# Camera_IR.net
KiCad netlist of a schematic drawn in EasyEDA
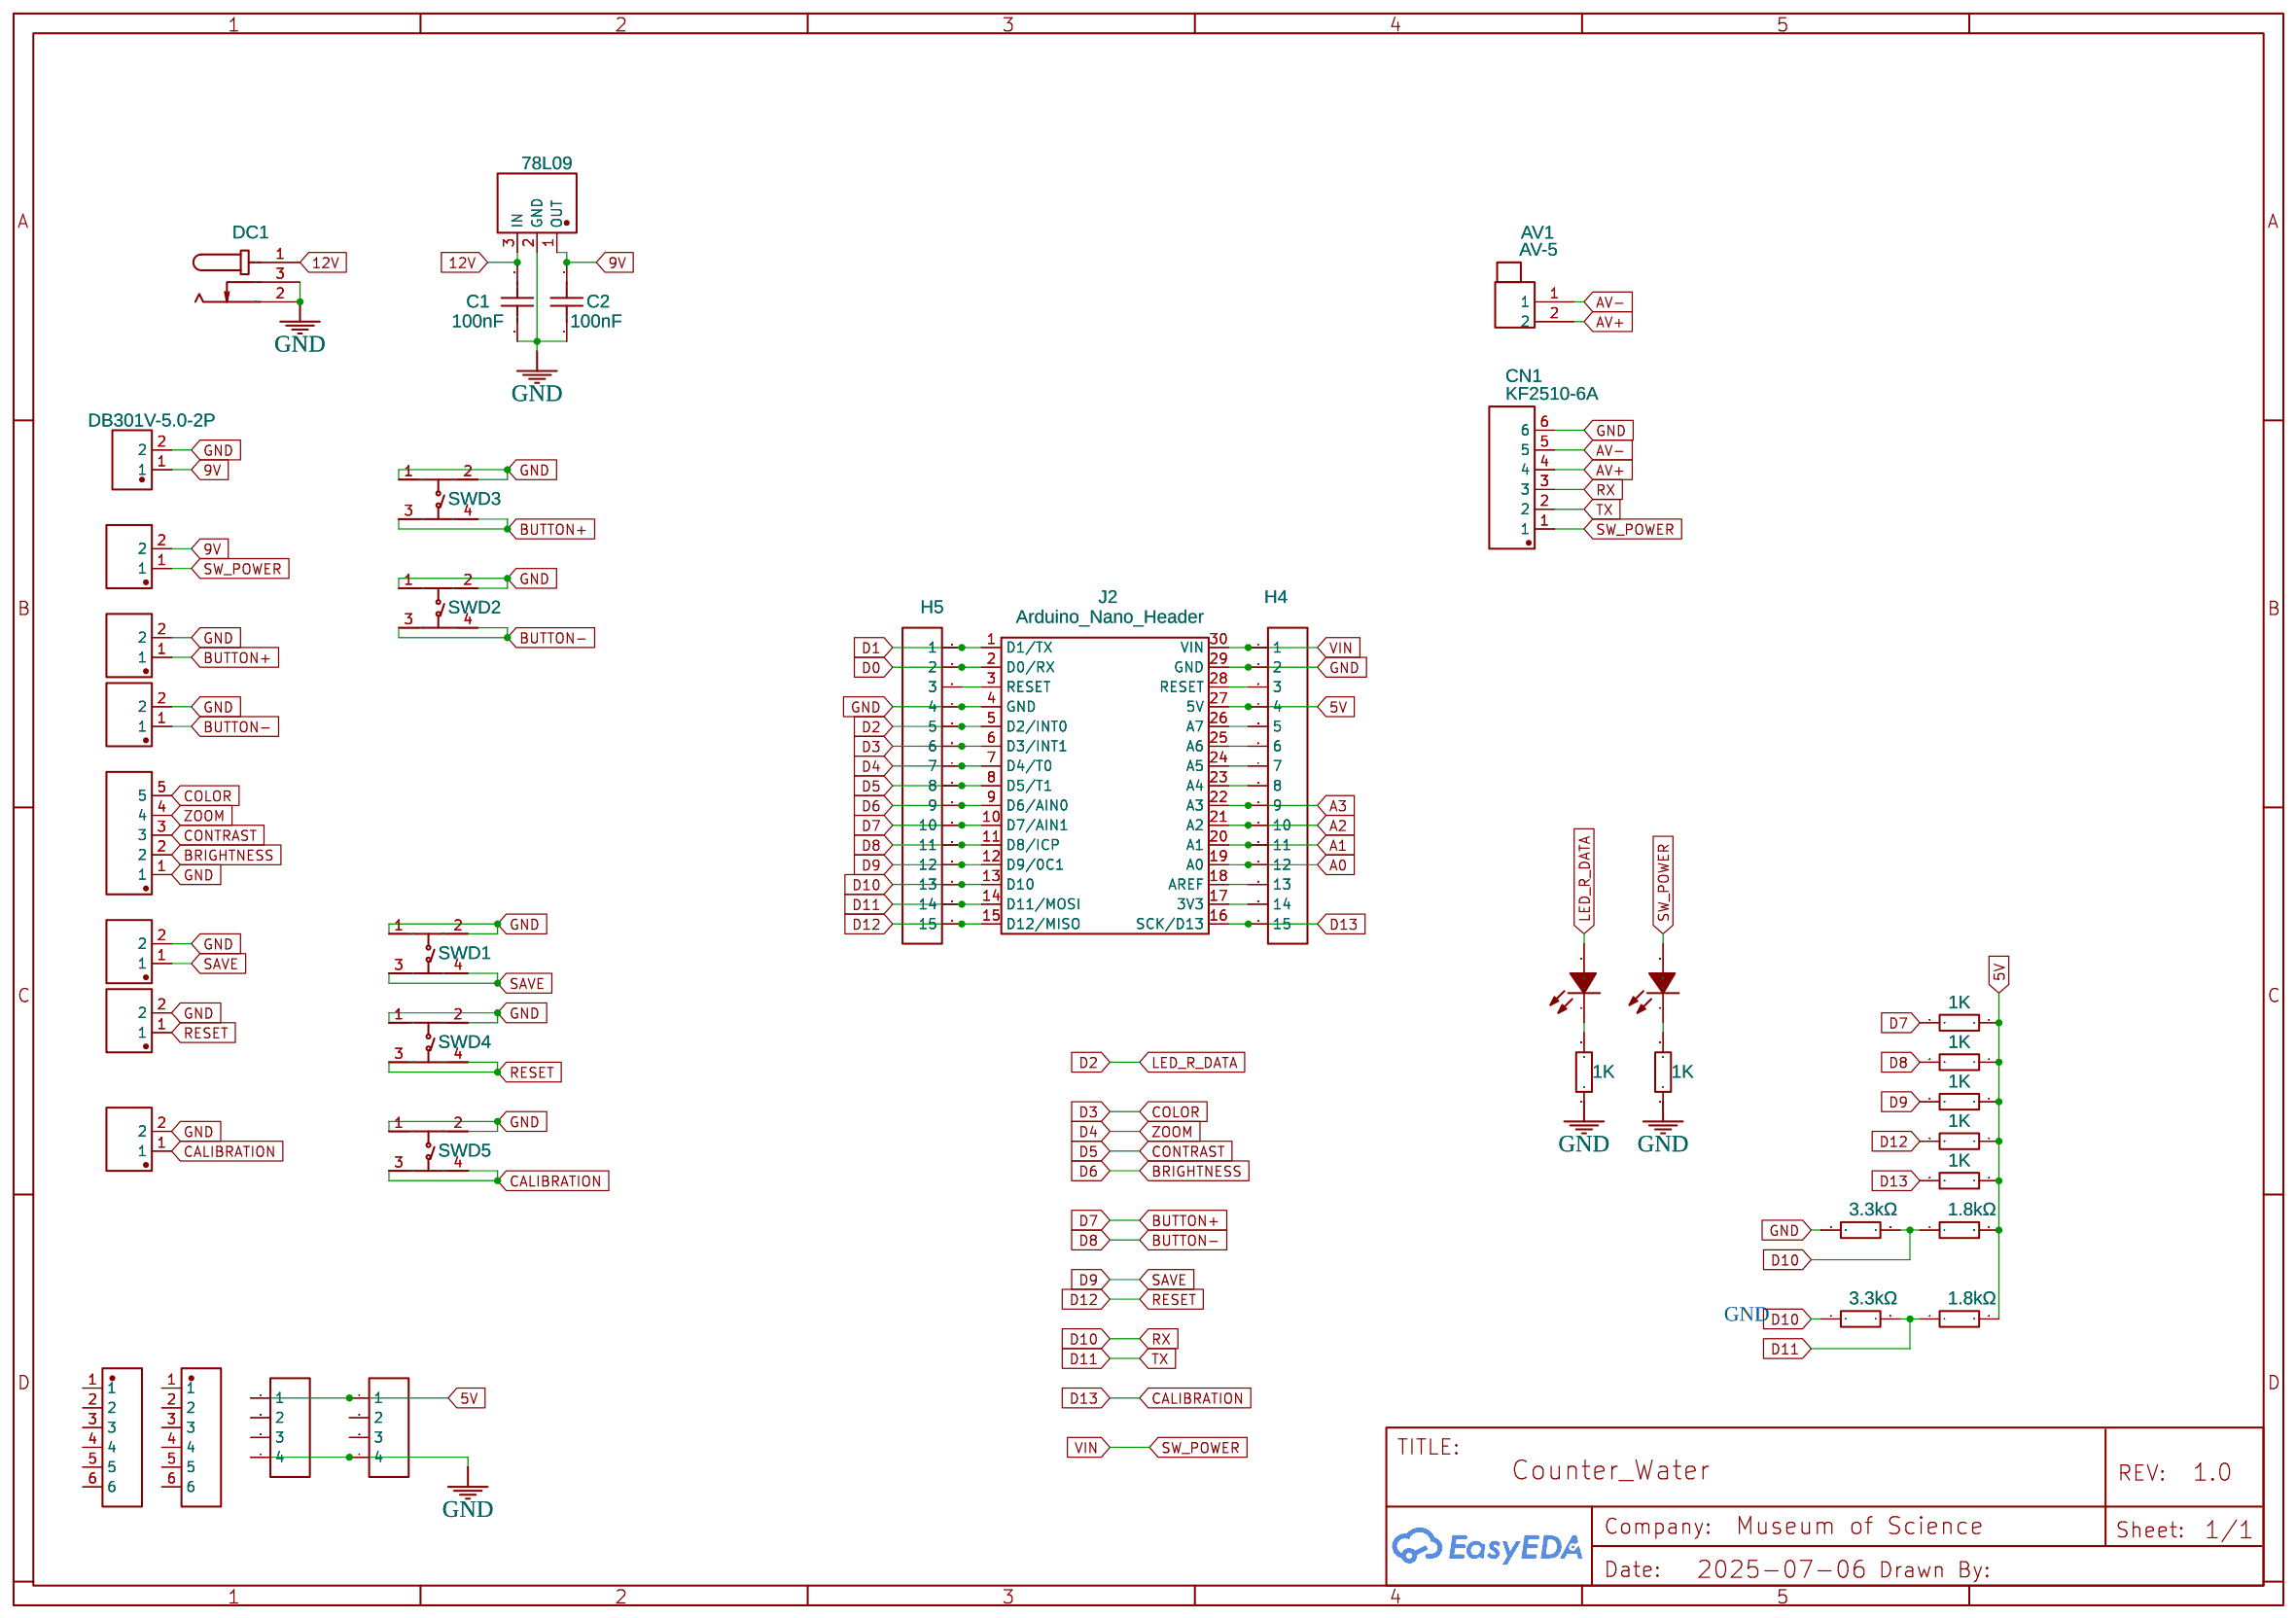
[diagram p0: schematic sheet]

(export (version "E")
  (design (tool "Eeschema 10.0.6"))
  (components
    (comp (ref "AV1")
      (value "AV-5")
      (fields (field (name "Manufacturer") "BOOMELE(博穆精密)"))
      (libsource (lib "") (part "AV-5"))
    )
    (comp (ref "C1")
      (value "100nF")
      (fields
        (field (name "Manufacturer Part") "CC0603KRX7R9BB104")
        (field (name "Manufacturer") "YAGEO(国巨)")
      )
      (libsource (lib "") (part "CC0603KRX7R9BB104"))
    )
    (comp (ref "C2")
      (value "100nF")
      (fields
        (field (name "Manufacturer Part") "CC0603KRX7R9BB104")
        (field (name "Manufacturer") "YAGEO(国巨)")
      )
      (libsource (lib "") (part "CC0603KRX7R9BB104"))
    )
    (comp (ref "CN1")
      (value "KF2510-6A")
      (fields (field (name "Manufacturer Part") "KF2510-6A针座"))
      (libsource (lib "") (part "KF2510-6A"))
    )
    (comp (ref "D7")
      (value "B+")
      (fields (field (name "Manufacturer Part") "KF2510-2A") (field (name "Manufacturer") "BOOMELE"))
      (libsource (lib "") (part "KF2510-2A"))
    )
    (comp (ref "D8")
      (value "B-")
      (fields (field (name "Manufacturer Part") "KF2510-2A") (field (name "Manufacturer") "BOOMELE"))
      (libsource (lib "") (part "KF2510-2A"))
    )
    (comp (ref "D9")
      (value "SAVE")
      (fields (field (name "Manufacturer Part") "KF2510-2A") (field (name "Manufacturer") "BOOMELE"))
      (libsource (lib "") (part "KF2510-2A"))
    )
    (comp (ref "D12")
      (value "RESET")
      (fields (field (name "Manufacturer Part") "KF2510-2A") (field (name "Manufacturer") "BOOMELE"))
      (libsource (lib "") (part "KF2510-2A"))
    )
    (comp (ref "D13")
      (value "FFC")
      (fields (field (name "Manufacturer Part") "KF2510-2A") (field (name "Manufacturer") "BOOMELE"))
      (libsource (lib "") (part "KF2510-2A"))
    )
    (comp (ref "DC1")
      (value "DC")
      (fields (field (name "Manufacturer Part") "DC005-2.0MM") (field (name "Manufacturer") "SOFNG"))
      (libsource (lib "") (part "DC005-2.0MM"))
    )
    (comp (ref "ERL1")
      (value "1K")
      (fields (field (name "Manufacturer Part") "0603WAF1001T5E") (field (name "Manufacturer") "UniOhm"))
      (libsource (lib "") (part "0603WAF1001T5E_1"))
    )
    (comp (ref "ERL2")
      (value "1K")
      (fields (field (name "Manufacturer Part") "0603WAF1001T5E") (field (name "Manufacturer") "UniOhm"))
      (libsource (lib "") (part "0603WAF1001T5E"))
    )
    (comp (ref "ERL4")
      (value "1K")
      (fields (field (name "Manufacturer Part") "0603WAF1001T5E") (field (name "Manufacturer") "UniOhm"))
      (libsource (lib "") (part "0603WAF1001T5E_1"))
    )
    (comp (ref "ERL6")
      (value "1K")
      (fields (field (name "Manufacturer Part") "0603WAF1001T5E") (field (name "Manufacturer") "UniOhm"))
      (libsource (lib "") (part "0603WAF1001T5E"))
    )
    (comp (ref "ERL9")
      (value "1K")
      (fields (field (name "Manufacturer Part") "0603WAF1001T5E") (field (name "Manufacturer") "UniOhm"))
      (libsource (lib "") (part "0603WAF1001T5E"))
    )
    (comp (ref "ERL11")
      (value "1K")
      (fields (field (name "Manufacturer Part") "0603WAF1001T5E") (field (name "Manufacturer") "UniOhm"))
      (libsource (lib "") (part "0603WAF1001T5E"))
    )
    (comp (ref "ERL12")
      (value "1K")
      (fields (field (name "Manufacturer Part") "0603WAF1001T5E") (field (name "Manufacturer") "UniOhm"))
      (libsource (lib "") (part "0603WAF1001T5E"))
    )
    (comp (ref "H4") (value "HDR-F-2.54_1x15") (libsource (lib "") (part "HDR-F-2.54_1x15")))
    (comp (ref "H5") (value "HDR-F-2.54_1x15") (libsource (lib "") (part "HDR-F-2.54_1x15_1")))
    (comp (ref "J2") (value "Arduino_Nano_Header") (libsource (lib "") (part "Arduino_Nano_Header")))
    (comp (ref "J6") (value "HDR-M-2.54_1x4") (libsource (lib "") (part "HDR-M-2.54_1x4")))
    (comp (ref "J7") (value "HDR-M-2.54_1x4") (libsource (lib "") (part "HDR-M-2.54_1x4")))
    (comp (ref "LED4")
      (value "KT-0603R")
      (fields (field (name "Manufacturer") "KENTO"))
      (libsource (lib "") (part "KT-0603R"))
    )
    (comp (ref "LED5")
      (value "KT-0603R")
      (fields (field (name "Manufacturer") "KENTO"))
      (libsource (lib "") (part "KT-0603R"))
    )
    (comp (ref "P1")
      (value "KF2510-5A")
      (fields (field (name "Manufacturer Part") "2510-5A") (field (name "Manufacturer") "BOOMELE(博穆精密)"))
      (libsource (lib "") (part "KF2510-5A"))
    )
    (comp (ref "P2")
      (value "H6")
      (fields (field (name "Manufacturer Part") "2.54-1*6P母") (field (name "Manufacturer") "BOOMELE(博穆精密)"))
      (libsource (lib "") (part "Header-Female-2.54_1x6"))
    )
    (comp (ref "P3")
      (value "H6")
      (fields (field (name "Manufacturer Part") "2.54-1*6P母") (field (name "Manufacturer") "BOOMELE(博穆精密)"))
      (libsource (lib "") (part "Header-Female-2.54_1x6"))
    )
    (comp (ref "R1")
      (value "1.8kΩ")
      (fields
        (field (name "Manufacturer Part") "0603WAF1801T5E")
        (field (name "Manufacturer") "UNI-ROYAL(厚声)")
      )
      (libsource (lib "") (part "0603WAF1801T5E"))
    )
    (comp (ref "R2")
      (value "1.8kΩ")
      (fields
        (field (name "Manufacturer Part") "0603WAF1801T5E")
        (field (name "Manufacturer") "UNI-ROYAL(厚声)")
      )
      (libsource (lib "") (part "0603WAF1801T5E"))
    )
    (comp (ref "R3")
      (value "3.3kΩ")
      (fields
        (field (name "Manufacturer Part") "0402WGF3301TCE")
        (field (name "Manufacturer") "UNI-ROYAL(厚声)")
      )
      (libsource (lib "") (part "0402WGF3301TCE"))
    )
    (comp (ref "R4")
      (value "3.3kΩ")
      (fields
        (field (name "Manufacturer Part") "0402WGF3301TCE")
        (field (name "Manufacturer") "UNI-ROYAL(厚声)")
      )
      (libsource (lib "") (part "0402WGF3301TCE"))
    )
    (comp (ref "SWD1")
      (value "TC-6610-7-160G")
      (fields (field (name "Manufacturer") "HCTL(华灿天禄)"))
      (libsource (lib "") (part "TC-6610-7-160G"))
    )
    (comp (ref "SWD2")
      (value "TC-6610-7-160G")
      (fields (field (name "Manufacturer") "HCTL(华灿天禄)"))
      (libsource (lib "") (part "TC-6610-7-160G"))
    )
    (comp (ref "SWD3")
      (value "TC-6610-7-160G")
      (fields (field (name "Manufacturer") "HCTL(华灿天禄)"))
      (libsource (lib "") (part "TC-6610-7-160G"))
    )
    (comp (ref "SWD4")
      (value "TC-6610-7-160G")
      (fields (field (name "Manufacturer") "HCTL(华灿天禄)"))
      (libsource (lib "") (part "TC-6610-7-160G"))
    )
    (comp (ref "SWD5")
      (value "TC-6610-7-160G")
      (fields (field (name "Manufacturer") "HCTL(华灿天禄)"))
      (libsource (lib "") (part "TC-6610-7-160G"))
    )
    (comp (ref "SW_P")
      (value "SW_P")
      (fields (field (name "Manufacturer Part") "KF2510-2A") (field (name "Manufacturer") "BOOMELE"))
      (libsource (lib "") (part "KF2510-2A_1"))
    )
    (comp (ref "U1")
      (value "78L09")
      (fields (field (name "Manufacturer") "CBI(创基)"))
      (libsource (lib "") (part "78L09U 78L09"))
    )
    (comp (ref "U3")
      (value "DB301V-5.0-2P")
      (fields
        (field (name "Manufacturer Part") "DB301V-5.0-2P-BU-S")
        (field (name "Manufacturer") "DORABO(地博电气)")
      )
      (libsource (lib "") (part "DB301V-5.0-2P"))
    )
  )
  (nets
    (net (code "1") (name "5V") (class "Default")
      (node (ref "ERL11") (pin "1") (pinfunction "1_1") (pintype "input"))
      (node (ref "ERL12") (pin "1") (pinfunction "1_1") (pintype "input"))
      (node (ref "ERL2") (pin "1") (pinfunction "1_1") (pintype "input"))
      (node (ref "ERL6") (pin "1") (pinfunction "1_1") (pintype "input"))
      (node (ref "ERL9") (pin "1") (pinfunction "1_1") (pintype "input"))
      (node (ref "H4") (pin "4") (pinfunction "4_4") (pintype "unspecified"))
      (node (ref "J2") (pin "27") (pinfunction "5V_27") (pintype "unspecified"))
      (node (ref "J6") (pin "1") (pinfunction "1_1") (pintype "unspecified"))
      (node (ref "J7") (pin "1") (pinfunction "1_1") (pintype "unspecified"))
      (node (ref "R1") (pin "2") (pinfunction "2_2") (pintype "input"))
      (node (ref "R2") (pin "2") (pinfunction "2_2") (pintype "input"))
    )
    (net (code "2") (name "9V") (class "Default")
      (node (ref "C2") (pin "2") (pinfunction "2_2") (pintype "unspecified"))
      (node (ref "SW_P") (pin "2") (pinfunction "2_2") (pintype "unspecified"))
      (node (ref "U1") (pin "1") (pinfunction "OUT_1") (pintype "unspecified"))
      (node (ref "U3") (pin "1") (pinfunction "1_1") (pintype "unspecified"))
    )
    (net (code "3") (name "12V") (class "Default")
      (node (ref "C1") (pin "2") (pinfunction "2_2") (pintype "unspecified"))
      (node (ref "DC1") (pin "1") (pinfunction "1_1") (pintype "unspecified"))
      (node (ref "U1") (pin "3") (pinfunction "IN_3") (pintype "unspecified"))
    )
    (net (code "4") (name "A0") (class "Default")
      (node (ref "H4") (pin "12") (pinfunction "12_12") (pintype "unspecified"))
      (node (ref "J2") (pin "19") (pinfunction "A0_19") (pintype "unspecified"))
    )
    (net (code "5") (name "A1") (class "Default")
      (node (ref "H4") (pin "11") (pinfunction "11_11") (pintype "unspecified"))
      (node (ref "J2") (pin "20") (pinfunction "A1_20") (pintype "unspecified"))
    )
    (net (code "6") (name "A2") (class "Default")
      (node (ref "H4") (pin "10") (pinfunction "10_10") (pintype "unspecified"))
      (node (ref "J2") (pin "21") (pinfunction "A2_21") (pintype "unspecified"))
    )
    (net (code "7") (name "A3") (class "Default")
      (node (ref "H4") (pin "9") (pinfunction "9_9") (pintype "unspecified"))
      (node (ref "J2") (pin "22") (pinfunction "A3_22") (pintype "unspecified"))
    )
    (net (code "8") (name "AV+") (class "Default")
      (node (ref "AV1") (pin "2") (pinfunction "2_2") (pintype "unspecified"))
      (node (ref "CN1") (pin "4") (pinfunction "4_4") (pintype "unspecified"))
    )
    (net (code "9") (name "AV-") (class "Default")
      (node (ref "AV1") (pin "1") (pinfunction "1_1") (pintype "unspecified"))
      (node (ref "CN1") (pin "5") (pinfunction "5_5") (pintype "unspecified"))
    )
    (net (code "10") (name "BRIGHTNESS") (class "Default")
      (node (ref "H5") (pin "9") (pinfunction "9_9") (pintype "unspecified"))
      (node (ref "J2") (pin "9") (pinfunction "D6/AIN0_9") (pintype "unspecified"))
      (node (ref "P1") (pin "2") (pinfunction "2_2") (pintype "unspecified"))
    )
    (net (code "11") (name "BUTTON+") (class "Default")
      (node (ref "D7") (pin "1") (pinfunction "1_1") (pintype "unspecified"))
      (node (ref "ERL6") (pin "2") (pinfunction "2_2") (pintype "input"))
      (node (ref "H5") (pin "10") (pinfunction "10_10") (pintype "unspecified"))
      (node (ref "J2") (pin "10") (pinfunction "D7/AIN1_10") (pintype "unspecified"))
      (node (ref "SWD3") (pin "3") (pinfunction "3_3") (pintype "unspecified"))
      (node (ref "SWD3") (pin "4") (pinfunction "4_4") (pintype "unspecified"))
    )
    (net (code "12") (name "BUTTON-") (class "Default")
      (node (ref "D8") (pin "1") (pinfunction "1_1") (pintype "unspecified"))
      (node (ref "ERL11") (pin "2") (pinfunction "2_2") (pintype "input"))
      (node (ref "H5") (pin "11") (pinfunction "11_11") (pintype "unspecified"))
      (node (ref "J2") (pin "11") (pinfunction "D8/ICP_11") (pintype "unspecified"))
      (node (ref "SWD2") (pin "3") (pinfunction "3_3") (pintype "unspecified"))
      (node (ref "SWD2") (pin "4") (pinfunction "4_4") (pintype "unspecified"))
    )
    (net (code "13") (name "CALIBRATION") (class "Default")
      (node (ref "D13") (pin "1") (pinfunction "1_1") (pintype "unspecified"))
      (node (ref "ERL2") (pin "2") (pinfunction "2_2") (pintype "input"))
      (node (ref "H4") (pin "15") (pinfunction "15_15") (pintype "unspecified"))
      (node (ref "J2") (pin "16") (pinfunction "SCK/D13_16") (pintype "unspecified"))
      (node (ref "SWD5") (pin "3") (pinfunction "3_3") (pintype "unspecified"))
      (node (ref "SWD5") (pin "4") (pinfunction "4_4") (pintype "unspecified"))
    )
    (net (code "14") (name "COLOR") (class "Default")
      (node (ref "H5") (pin "6") (pinfunction "6_6") (pintype "unspecified"))
      (node (ref "J2") (pin "6") (pinfunction "D3/INT1_6") (pintype "unspecified"))
      (node (ref "P1") (pin "5") (pinfunction "5_5") (pintype "unspecified"))
    )
    (net (code "15") (name "CONTRAST") (class "Default")
      (node (ref "H5") (pin "8") (pinfunction "8_8") (pintype "unspecified"))
      (node (ref "J2") (pin "8") (pinfunction "D5/T1_8") (pintype "unspecified"))
      (node (ref "P1") (pin "3") (pinfunction "3_3") (pintype "unspecified"))
    )
    (net (code "16") (name "D0") (class "Default")
      (node (ref "H5") (pin "2") (pinfunction "2_2") (pintype "unspecified"))
      (node (ref "J2") (pin "2") (pinfunction "D0/RX_2") (pintype "unspecified"))
    )
    (net (code "17") (name "D1") (class "Default")
      (node (ref "H5") (pin "1") (pinfunction "1_1") (pintype "unspecified"))
      (node (ref "J2") (pin "1") (pinfunction "D1/TX_1") (pintype "unspecified"))
    )
    (net (code "18") (name "D2") (class "Default")
      (node (ref "H5") (pin "5") (pinfunction "5_5") (pintype "unspecified"))
      (node (ref "J2") (pin "5") (pinfunction "D2/INT0_5") (pintype "unspecified"))
      (node (ref "LED5") (pin "2") (pinfunction "A_2") (pintype "unspecified"))
    )
    (net (code "19") (name "D4") (class "Default")
      (node (ref "H5") (pin "7") (pinfunction "7_7") (pintype "unspecified"))
      (node (ref "J2") (pin "7") (pinfunction "D4/T0_7") (pintype "unspecified"))
      (node (ref "P1") (pin "4") (pinfunction "4_4") (pintype "unspecified"))
    )
    (net (code "20") (name "D9") (class "Default")
      (node (ref "D9") (pin "1") (pinfunction "1_1") (pintype "unspecified"))
      (node (ref "ERL9") (pin "2") (pinfunction "2_2") (pintype "input"))
      (node (ref "H5") (pin "12") (pinfunction "12_12") (pintype "unspecified"))
      (node (ref "J2") (pin "12") (pinfunction "D9/0C1_12") (pintype "unspecified"))
      (node (ref "SWD1") (pin "3") (pinfunction "3_3") (pintype "unspecified"))
      (node (ref "SWD1") (pin "4") (pinfunction "4_4") (pintype "unspecified"))
    )
    (net (code "21") (name "D10") (class "Default")
      (node (ref "CN1") (pin "3") (pinfunction "3_3") (pintype "unspecified"))
      (node (ref "H5") (pin "13") (pinfunction "13_13") (pintype "unspecified"))
      (node (ref "J2") (pin "13") (pinfunction "D10_13") (pintype "unspecified"))
      (node (ref "R1") (pin "1") (pinfunction "1_1") (pintype "input"))
      (node (ref "R3") (pin "2") (pinfunction "2_2") (pintype "input"))
      (node (ref "R4") (pin "1") (pinfunction "1_1") (pintype "input"))
    )
    (net (code "22") (name "D11") (class "Default")
      (node (ref "CN1") (pin "2") (pinfunction "2_2") (pintype "unspecified"))
      (node (ref "H5") (pin "14") (pinfunction "14_14") (pintype "unspecified"))
      (node (ref "J2") (pin "14") (pinfunction "D11/MOSI_14") (pintype "unspecified"))
      (node (ref "R2") (pin "1") (pinfunction "1_1") (pintype "input"))
      (node (ref "R4") (pin "2") (pinfunction "2_2") (pintype "input"))
    )
    (net (code "23") (name "D12") (class "Default")
      (node (ref "D12") (pin "1") (pinfunction "1_1") (pintype "unspecified"))
      (node (ref "ERL12") (pin "2") (pinfunction "2_2") (pintype "input"))
      (node (ref "H5") (pin "15") (pinfunction "15_15") (pintype "unspecified"))
      (node (ref "J2") (pin "15") (pinfunction "D12/MISO_15") (pintype "unspecified"))
      (node (ref "SWD4") (pin "3") (pinfunction "3_3") (pintype "unspecified"))
      (node (ref "SWD4") (pin "4") (pinfunction "4_4") (pintype "unspecified"))
    )
    (net (code "24") (name "GND") (class "Default")
      (node (ref "C1") (pin "1") (pinfunction "1_1") (pintype "unspecified"))
      (node (ref "C2") (pin "1") (pinfunction "1_1") (pintype "unspecified"))
      (node (ref "CN1") (pin "6") (pinfunction "6_6") (pintype "unspecified"))
      (node (ref "D12") (pin "2") (pinfunction "2_2") (pintype "unspecified"))
      (node (ref "D13") (pin "2") (pinfunction "2_2") (pintype "unspecified"))
      (node (ref "D7") (pin "2") (pinfunction "2_2") (pintype "unspecified"))
      (node (ref "D8") (pin "2") (pinfunction "2_2") (pintype "unspecified"))
      (node (ref "D9") (pin "2") (pinfunction "2_2") (pintype "unspecified"))
      (node (ref "DC1") (pin "2") (pinfunction "2_2") (pintype "unspecified"))
      (node (ref "DC1") (pin "3") (pinfunction "3_3") (pintype "unspecified"))
      (node (ref "ERL1") (pin "1") (pinfunction "1_1") (pintype "input"))
      (node (ref "ERL4") (pin "1") (pinfunction "1_1") (pintype "input"))
      (node (ref "H4") (pin "2") (pinfunction "2_2") (pintype "unspecified"))
      (node (ref "H5") (pin "4") (pinfunction "4_4") (pintype "unspecified"))
      (node (ref "J2") (pin "29") (pinfunction "GND_29") (pintype "unspecified"))
      (node (ref "J2") (pin "4") (pinfunction "GND_4") (pintype "unspecified"))
      (node (ref "J6") (pin "4") (pinfunction "4_4") (pintype "unspecified"))
      (node (ref "J7") (pin "4") (pinfunction "4_4") (pintype "unspecified"))
      (node (ref "P1") (pin "1") (pinfunction "1_1") (pintype "unspecified"))
      (node (ref "R3") (pin "1") (pinfunction "1_1") (pintype "input"))
      (node (ref "SWD1") (pin "1") (pinfunction "1_1") (pintype "unspecified"))
      (node (ref "SWD1") (pin "2") (pinfunction "2_2") (pintype "unspecified"))
      (node (ref "SWD2") (pin "1") (pinfunction "1_1") (pintype "unspecified"))
      (node (ref "SWD2") (pin "2") (pinfunction "2_2") (pintype "unspecified"))
      (node (ref "SWD3") (pin "1") (pinfunction "1_1") (pintype "unspecified"))
      (node (ref "SWD3") (pin "2") (pinfunction "2_2") (pintype "unspecified"))
      (node (ref "SWD4") (pin "1") (pinfunction "1_1") (pintype "unspecified"))
      (node (ref "SWD4") (pin "2") (pinfunction "2_2") (pintype "unspecified"))
      (node (ref "SWD5") (pin "1") (pinfunction "1_1") (pintype "unspecified"))
      (node (ref "SWD5") (pin "2") (pinfunction "2_2") (pintype "unspecified"))
      (node (ref "U1") (pin "2") (pinfunction "GND_2") (pintype "unspecified"))
      (node (ref "U3") (pin "2") (pinfunction "2_2") (pintype "unspecified"))
    )
    (net (code "25") (name "Net-(H4-Pad3)") (class "Default")
      (node (ref "H4") (pin "3") (pinfunction "3_3") (pintype "unspecified"))
      (node (ref "J2") (pin "28") (pinfunction "RESET_28") (pintype "unspecified"))
    )
    (net (code "26") (name "Net-(H5-Pad3)") (class "Default")
      (node (ref "H5") (pin "3") (pinfunction "3_3") (pintype "unspecified"))
      (node (ref "J2") (pin "3") (pinfunction "RESET_3") (pintype "unspecified"))
    )
    (net (code "27") (name "Net-(J2-3V3)") (class "Default")
      (node (ref "H4") (pin "14") (pinfunction "14_14") (pintype "unspecified"))
      (node (ref "J2") (pin "17") (pinfunction "3V3_17") (pintype "unspecified"))
    )
    (net (code "28") (name "Net-(J2-A4)") (class "Default")
      (node (ref "H4") (pin "8") (pinfunction "8_8") (pintype "unspecified"))
      (node (ref "J2") (pin "23") (pinfunction "A4_23") (pintype "unspecified"))
    )
    (net (code "29") (name "Net-(J2-A5)") (class "Default")
      (node (ref "H4") (pin "7") (pinfunction "7_7") (pintype "unspecified"))
      (node (ref "J2") (pin "24") (pinfunction "A5_24") (pintype "unspecified"))
    )
    (net (code "30") (name "Net-(J2-A6)") (class "Default")
      (node (ref "H4") (pin "6") (pinfunction "6_6") (pintype "unspecified"))
      (node (ref "J2") (pin "25") (pinfunction "A6_25") (pintype "unspecified"))
    )
    (net (code "31") (name "Net-(J2-A7)") (class "Default")
      (node (ref "H4") (pin "5") (pinfunction "5_5") (pintype "unspecified"))
      (node (ref "J2") (pin "26") (pinfunction "A7_26") (pintype "unspecified"))
    )
    (net (code "32") (name "Net-(J2-AREF)") (class "Default")
      (node (ref "H4") (pin "13") (pinfunction "13_13") (pintype "unspecified"))
      (node (ref "J2") (pin "18") (pinfunction "AREF_18") (pintype "unspecified"))
    )
    (net (code "33") (name "Net-(LED4-K)") (class "Default")
      (node (ref "ERL4") (pin "2") (pinfunction "2_2") (pintype "input"))
      (node (ref "LED4") (pin "1") (pinfunction "K_1") (pintype "unspecified"))
    )
    (net (code "34") (name "Net-(LED5-K)") (class "Default")
      (node (ref "ERL1") (pin "2") (pinfunction "2_2") (pintype "input"))
      (node (ref "LED5") (pin "1") (pinfunction "K_1") (pintype "unspecified"))
    )
    (net (code "35") (name "SW_POWER") (class "Default")
      (node (ref "CN1") (pin "1") (pinfunction "1_1") (pintype "unspecified"))
      (node (ref "H4") (pin "1") (pinfunction "1_1") (pintype "unspecified"))
      (node (ref "J2") (pin "30") (pinfunction "VIN_30") (pintype "unspecified"))
      (node (ref "LED4") (pin "2") (pinfunction "A_2") (pintype "unspecified"))
      (node (ref "SW_P") (pin "1") (pinfunction "1_1") (pintype "unspecified"))
    )
    (net (code "36") (name "unconnected-(J6-Pad2)") (class "Default")
      (node (ref "J6") (pin "2") (pinfunction "2_2") (pintype "unspecified"))
    )
    (net (code "37") (name "unconnected-(J6-Pad3)") (class "Default")
      (node (ref "J6") (pin "3") (pinfunction "3_3") (pintype "unspecified"))
    )
    (net (code "38") (name "unconnected-(J7-Pad2)") (class "Default")
      (node (ref "J7") (pin "2") (pinfunction "2_2") (pintype "unspecified"))
    )
    (net (code "39") (name "unconnected-(J7-Pad3)") (class "Default")
      (node (ref "J7") (pin "3") (pinfunction "3_3") (pintype "unspecified"))
    )
    (net (code "40") (name "unconnected-(P2-Pad1)") (class "Default")
      (node (ref "P2") (pin "1") (pinfunction "1_1") (pintype "unspecified"))
    )
    (net (code "41") (name "unconnected-(P2-Pad2)") (class "Default")
      (node (ref "P2") (pin "2") (pinfunction "2_2") (pintype "unspecified"))
    )
    (net (code "42") (name "unconnected-(P2-Pad3)") (class "Default")
      (node (ref "P2") (pin "3") (pinfunction "3_3") (pintype "unspecified"))
    )
    (net (code "43") (name "unconnected-(P2-Pad4)") (class "Default")
      (node (ref "P2") (pin "4") (pinfunction "4_4") (pintype "unspecified"))
    )
    (net (code "44") (name "unconnected-(P2-Pad5)") (class "Default")
      (node (ref "P2") (pin "5") (pinfunction "5_5") (pintype "unspecified"))
    )
    (net (code "45") (name "unconnected-(P2-Pad6)") (class "Default")
      (node (ref "P2") (pin "6") (pinfunction "6_6") (pintype "unspecified"))
    )
    (net (code "46") (name "unconnected-(P3-Pad1)") (class "Default")
      (node (ref "P3") (pin "1") (pinfunction "1_1") (pintype "unspecified"))
    )
    (net (code "47") (name "unconnected-(P3-Pad2)") (class "Default")
      (node (ref "P3") (pin "2") (pinfunction "2_2") (pintype "unspecified"))
    )
    (net (code "48") (name "unconnected-(P3-Pad3)") (class "Default")
      (node (ref "P3") (pin "3") (pinfunction "3_3") (pintype "unspecified"))
    )
    (net (code "49") (name "unconnected-(P3-Pad4)") (class "Default")
      (node (ref "P3") (pin "4") (pinfunction "4_4") (pintype "unspecified"))
    )
    (net (code "50") (name "unconnected-(P3-Pad5)") (class "Default")
      (node (ref "P3") (pin "5") (pinfunction "5_5") (pintype "unspecified"))
    )
    (net (code "51") (name "unconnected-(P3-Pad6)") (class "Default")
      (node (ref "P3") (pin "6") (pinfunction "6_6") (pintype "unspecified"))
    )
  )
)
